# Bus_Extender.net
KiCad netlist of a schematic drawn in Altium Designer
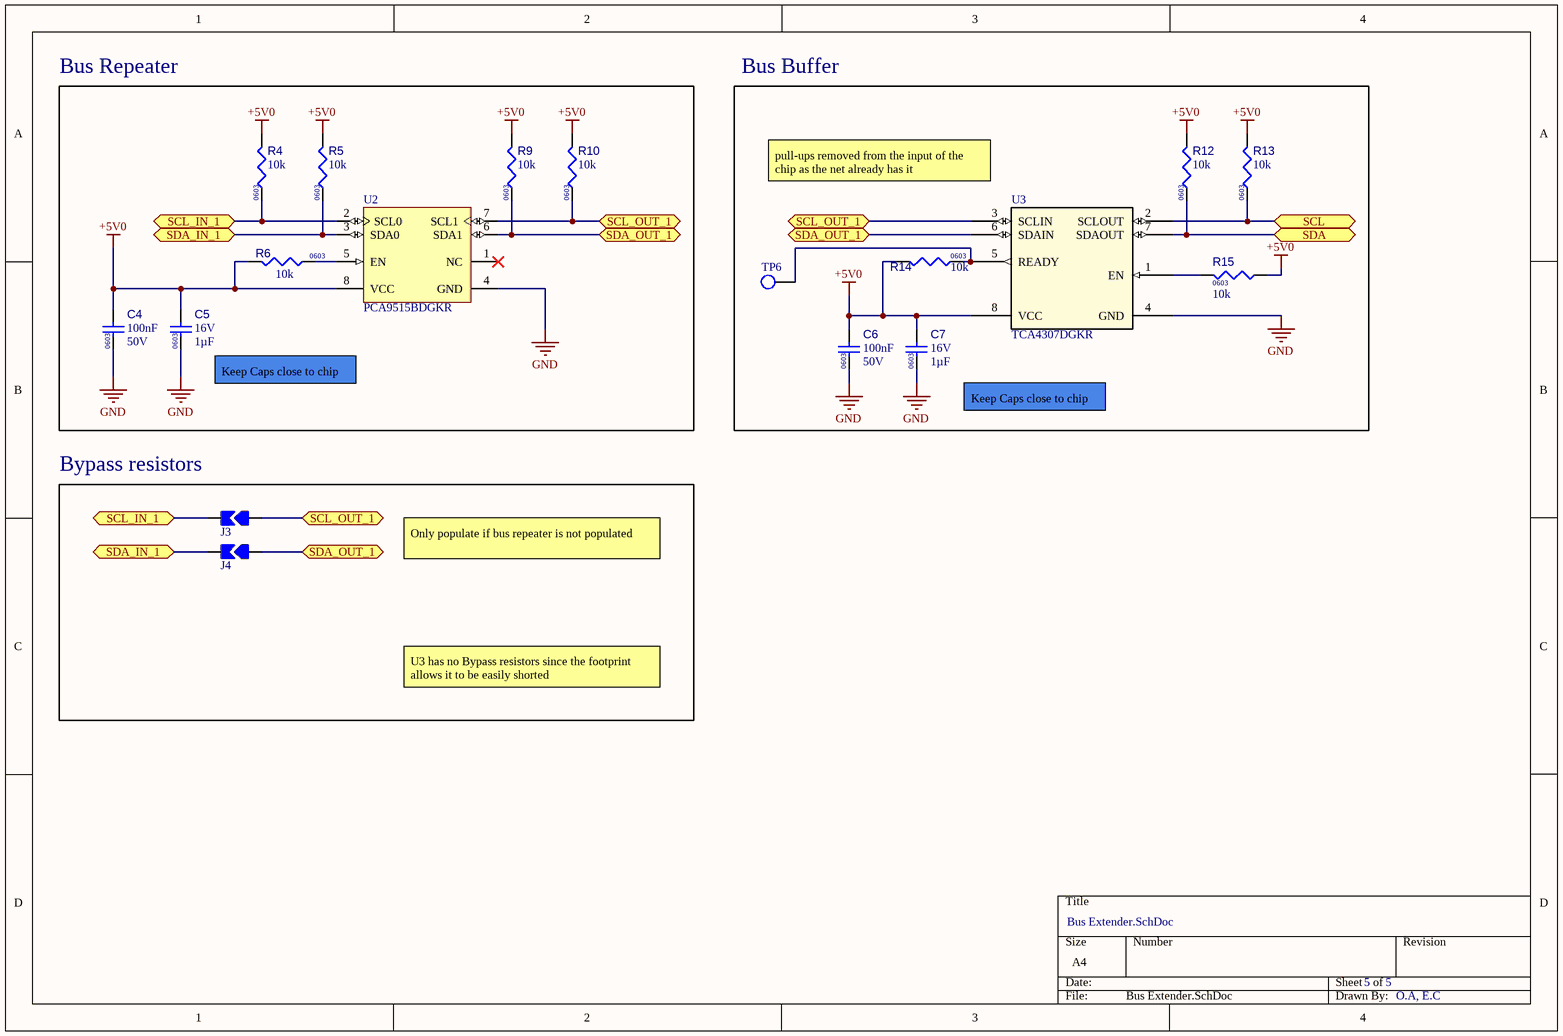
[diagram p0: Bus Extender.SchDoc]

(export (version "E")
  (design (tool "Eeschema 10.0.6"))
  (components
    (comp (ref "C4")
      (value "100nF")
      (footprint "CAPC1608X90X40NL10T20")
      (description "Chip Capacitor, 100 nF, +/- 10%, 50 V, 0603 (1608 Metric)")
      (fields
        (field (name "TOLERANCE") "10%")
        (field (name "VOLTAGE RATING") "50V")
        (field (name "CASE/PACKAGE") "0603")
        (field (name "Comment") "Capacitor 100 nF +/-10% 50 V 0603")
      )
      (libsource (lib "hawaiirobotics") (part "CAP-NP-2"))
    )
    (comp (ref "C5")
      (value "1µF")
      (footprint "CAPC1608X90X35NL15T15")
      (description "Chip Capacitor, 1 uF, +/- 10%, 16 V, 0603 (1608 Metric)")
      (fields
        (field (name "CASE/PACKAGE") "0603")
        (field (name "VOLTAGE RATING") "16V")
        (field (name "TOLERANCE") "10%")
        (field (name "Comment") "Capacitor 1uF +/- 10% 16V 0603")
      )
      (libsource (lib "hawaiirobotics") (part "CAP-NP-2"))
    )
    (comp (ref "C6")
      (value "100nF")
      (footprint "CAPC1608X90X40NL10T20")
      (description "Chip Capacitor, 100 nF, +/- 10%, 50 V, 0603 (1608 Metric)")
      (fields
        (field (name "TOLERANCE") "10%")
        (field (name "VOLTAGE RATING") "50V")
        (field (name "CASE/PACKAGE") "0603")
        (field (name "Comment") "Capacitor 100 nF +/-10% 50 V 0603")
      )
      (libsource (lib "hawaiirobotics") (part "CAP-NP-2"))
    )
    (comp (ref "C7")
      (value "1µF")
      (footprint "CAPC1608X90X35NL15T15")
      (description "Chip Capacitor, 1 uF, +/- 10%, 16 V, 0603 (1608 Metric)")
      (fields
        (field (name "CASE/PACKAGE") "0603")
        (field (name "VOLTAGE RATING") "16V")
        (field (name "TOLERANCE") "10%")
        (field (name "Comment") "Capacitor 1uF +/- 10% 16V 0603")
      )
      (libsource (lib "hawaiirobotics") (part "CAP-NP-2"))
    )
    (comp (ref "J3")
      (value "Solder jumper")
      (footprint "New footprint 1")
      (libsource (lib "hawaiirobotics") (part "New symbol 1"))
    )
    (comp (ref "J4")
      (value "Solder jumper")
      (footprint "New footprint 1")
      (libsource (lib "hawaiirobotics") (part "New symbol 1"))
    )
    (comp (ref "R4")
      (value "10k")
      (footprint "RESC1608X55X25NL10T15")
      (description "Chip Resistor, 10 KOhm, +/- 1%, 01 W, -55 to 155 degC, 0603 (1608 Metric)")
      (fields
        (field (name "CASE/PACKAGE") "0603")
        (field (name "POWER") "100mW")
        (field (name "TOLERANCE") "1%")
      )
      (libsource (lib "hawaiirobotics") (part "RES-2"))
    )
    (comp (ref "R5")
      (value "10k")
      (footprint "RESC1608X55X25NL10T15")
      (description "Chip Resistor, 10 KOhm, +/- 1%, 01 W, -55 to 155 degC, 0603 (1608 Metric)")
      (fields
        (field (name "CASE/PACKAGE") "0603")
        (field (name "POWER") "100mW")
        (field (name "TOLERANCE") "1%")
      )
      (libsource (lib "hawaiirobotics") (part "RES-2"))
    )
    (comp (ref "R6")
      (value "10k")
      (footprint "RESC1608X55X25NL10T15")
      (description "Chip Resistor, 10 KOhm, +/- 1%, 01 W, -55 to 155 degC, 0603 (1608 Metric)")
      (fields
        (field (name "CASE/PACKAGE") "0603")
        (field (name "POWER") "100mW")
        (field (name "TOLERANCE") "1%")
      )
      (libsource (lib "hawaiirobotics") (part "RES-2"))
    )
    (comp (ref "R9")
      (value "10k")
      (footprint "RESC1608X55X25NL10T15")
      (description "Chip Resistor, 10 KOhm, +/- 1%, 01 W, -55 to 155 degC, 0603 (1608 Metric)")
      (fields
        (field (name "CASE/PACKAGE") "0603")
        (field (name "POWER") "100mW")
        (field (name "TOLERANCE") "1%")
      )
      (libsource (lib "hawaiirobotics") (part "RES-2"))
    )
    (comp (ref "R10")
      (value "10k")
      (footprint "RESC1608X55X25NL10T15")
      (description "Chip Resistor, 10 KOhm, +/- 1%, 01 W, -55 to 155 degC, 0603 (1608 Metric)")
      (fields
        (field (name "CASE/PACKAGE") "0603")
        (field (name "POWER") "100mW")
        (field (name "TOLERANCE") "1%")
      )
      (libsource (lib "hawaiirobotics") (part "RES-2"))
    )
    (comp (ref "R12")
      (value "10k")
      (footprint "RESC1608X55X25NL10T15")
      (description "Chip Resistor, 10 KOhm, +/- 1%, 01 W, -55 to 155 degC, 0603 (1608 Metric)")
      (fields
        (field (name "CASE/PACKAGE") "0603")
        (field (name "POWER") "100mW")
        (field (name "TOLERANCE") "1%")
      )
      (libsource (lib "hawaiirobotics") (part "RES-2"))
    )
    (comp (ref "R13")
      (value "10k")
      (footprint "RESC1608X55X25NL10T15")
      (description "Chip Resistor, 10 KOhm, +/- 1%, 01 W, -55 to 155 degC, 0603 (1608 Metric)")
      (fields
        (field (name "CASE/PACKAGE") "0603")
        (field (name "POWER") "100mW")
        (field (name "TOLERANCE") "1%")
      )
      (libsource (lib "hawaiirobotics") (part "RES-2"))
    )
    (comp (ref "R14")
      (value "10k")
      (footprint "RESC1608X55X25NL10T15")
      (description "Chip Resistor, 10 KOhm, +/- 1%, 01 W, -55 to 155 degC, 0603 (1608 Metric)")
      (fields
        (field (name "CASE/PACKAGE") "0603")
        (field (name "POWER") "100mW")
        (field (name "TOLERANCE") "1%")
      )
      (libsource (lib "hawaiirobotics") (part "RES-2"))
    )
    (comp (ref "R15")
      (value "10k")
      (footprint "RESC1608X55X25NL10T15")
      (description "Chip Resistor, 10 KOhm, +/- 1%, 01 W, -55 to 155 degC, 0603 (1608 Metric)")
      (fields
        (field (name "CASE/PACKAGE") "0603")
        (field (name "POWER") "100mW")
        (field (name "TOLERANCE") "1%")
      )
      (libsource (lib "hawaiirobotics") (part "RES-2"))
    )
    (comp (ref "TP6")
      (value "RCUCTE")
      (footprint "FP-S2761-46R-MFG")
      (description "Test point")
      (libsource (lib "hawaiirobotics") (part "RCUCTE-Symbol-1"))
    )
    (comp (ref "U2")
      (value "PCA9515BDGKR")
      (footprint "DGK0008A_L")
      (description "Interface Circuit, BICMOS, PDSO8")
      (libsource (lib "hawaiirobotics") (part "TI-PCA9515B-MSOP_DGK-8"))
    )
    (comp (ref "U3")
      (value "TCA4307DGKR")
      (footprint "TCA4307DGKR-Footprint-1")
      (description "Interface Circuit, PDSO8")
      (libsource (lib "hawaiirobotics") (part "TCA4307DGKR-Symbol-1"))
    )
  )
  (nets
    (net (code "1") (name "+5V0") (class "Default")
      (node (ref "C4") (pin "2") (pinfunction "2_2") (pintype "passive"))
      (node (ref "C5") (pin "2") (pinfunction "2_2") (pintype "passive"))
      (node (ref "C6") (pin "2") (pinfunction "2_2") (pintype "passive"))
      (node (ref "C7") (pin "2") (pinfunction "2_2") (pintype "passive"))
      (node (ref "R10") (pin "2") (pinfunction "2_2") (pintype "passive"))
      (node (ref "R12") (pin "2") (pinfunction "2_2") (pintype "passive"))
      (node (ref "R13") (pin "2") (pinfunction "2_2") (pintype "passive"))
      (node (ref "R14") (pin "2") (pinfunction "2_2") (pintype "passive"))
      (node (ref "R15") (pin "1") (pinfunction "1_1") (pintype "passive"))
      (node (ref "R4") (pin "2") (pinfunction "2_2") (pintype "passive"))
      (node (ref "R5") (pin "2") (pinfunction "2_2") (pintype "passive"))
      (node (ref "R6") (pin "2") (pinfunction "2_2") (pintype "passive"))
      (node (ref "R9") (pin "2") (pinfunction "2_2") (pintype "passive"))
      (node (ref "U2") (pin "8") (pinfunction "VCC_8") (pintype "power_in"))
      (node (ref "U3") (pin "8") (pinfunction "VCC_8") (pintype "power_in"))
    )
    (net (code "2") (name "/SCL") (class "Default")
      (node (ref "R13") (pin "1") (pinfunction "1_1") (pintype "passive"))
      (node (ref "U3") (pin "2") (pinfunction "SCLOUT_2") (pintype "bidirectional"))
    )
    (net (code "3") (name "/SCL_IN_1") (class "Default")
      (node (ref "J3") (pin "2") (pinfunction "2_2") (pintype "passive"))
      (node (ref "R4") (pin "1") (pinfunction "1_1") (pintype "passive"))
      (node (ref "U2") (pin "2") (pinfunction "SCL0_2") (pintype "bidirectional"))
    )
    (net (code "4") (name "/SCL_OUT_1") (class "Default")
      (node (ref "J3") (pin "1") (pinfunction "1_1") (pintype "passive"))
      (node (ref "R10") (pin "1") (pinfunction "1_1") (pintype "passive"))
      (node (ref "U2") (pin "7") (pinfunction "SCL1_7") (pintype "bidirectional"))
      (node (ref "U3") (pin "3") (pinfunction "SCLIN_3") (pintype "bidirectional"))
    )
    (net (code "5") (name "/SDA") (class "Default")
      (node (ref "R12") (pin "1") (pinfunction "1_1") (pintype "passive"))
      (node (ref "U3") (pin "7") (pinfunction "SDAOUT_7") (pintype "bidirectional"))
    )
    (net (code "6") (name "/SDA_IN_1") (class "Default")
      (node (ref "J4") (pin "2") (pinfunction "2_2") (pintype "passive"))
      (node (ref "R5") (pin "1") (pinfunction "1_1") (pintype "passive"))
      (node (ref "U2") (pin "3") (pinfunction "SDA0_3") (pintype "bidirectional"))
    )
    (net (code "7") (name "/SDA_OUT_1") (class "Default")
      (node (ref "J4") (pin "1") (pinfunction "1_1") (pintype "passive"))
      (node (ref "R9") (pin "1") (pinfunction "1_1") (pintype "passive"))
      (node (ref "U2") (pin "6") (pinfunction "SDA1_6") (pintype "bidirectional"))
      (node (ref "U3") (pin "6") (pinfunction "SDAIN_6") (pintype "bidirectional"))
    )
    (net (code "8") (name "GND") (class "Default")
      (node (ref "C4") (pin "1") (pinfunction "1_1") (pintype "passive"))
      (node (ref "C5") (pin "1") (pinfunction "1_1") (pintype "passive"))
      (node (ref "C6") (pin "1") (pinfunction "1_1") (pintype "passive"))
      (node (ref "C7") (pin "1") (pinfunction "1_1") (pintype "passive"))
      (node (ref "U2") (pin "4") (pinfunction "GND_4") (pintype "power_in"))
      (node (ref "U3") (pin "4") (pinfunction "GND_4") (pintype "power_in"))
    )
    (net (code "9") (name "Net-(U2-EN)") (class "Default")
      (node (ref "R6") (pin "1") (pinfunction "1_1") (pintype "passive"))
      (node (ref "U2") (pin "5") (pinfunction "EN_5") (pintype "input"))
    )
    (net (code "10") (name "Net-(U3-EN)") (class "Default")
      (node (ref "R15") (pin "2") (pinfunction "2_2") (pintype "passive"))
      (node (ref "U3") (pin "1") (pinfunction "EN_1") (pintype "input"))
    )
    (net (code "11") (name "Net-(U3-READY)") (class "Default")
      (node (ref "R14") (pin "1") (pinfunction "1_1") (pintype "passive"))
      (node (ref "TP6") (pin "1") (pinfunction "1_1") (pintype "passive"))
      (node (ref "U3") (pin "5") (pinfunction "READY_5") (pintype "output"))
    )
    (net (code "12") (name "unconnected-(U2-NC-Pad1)") (class "Default")
      (node (ref "U2") (pin "1") (pinfunction "NC_1") (pintype "passive+no_connect"))
    )
  )
)
